# hub_exterior.net
KiCad netlist of a schematic drawn in EAGLE
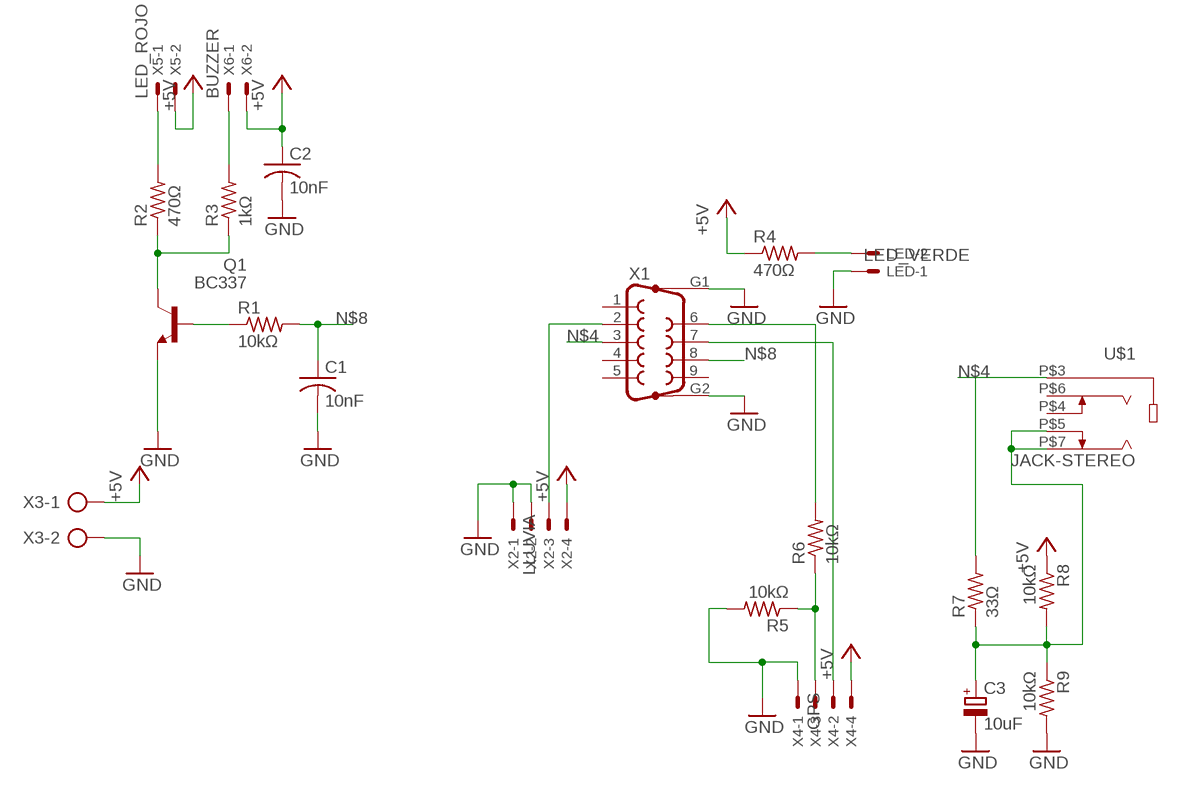
[diagram p0: schematic, sheet 1]

(export (version "E")
  (design (tool "Eeschema 10.0.6"))
  (components
    (comp (ref "C1")
      (value "10nF")
      (footprint "eagle-import:C050-025X075")
      (libsource (lib "eagle-import") (part "C-US050-025X075"))
    )
    (comp (ref "C2")
      (value "10nF")
      (footprint "eagle-import:C050-025X075")
      (libsource (lib "eagle-import") (part "C-US050-025X075"))
    )
    (comp (ref "C3")
      (value "10uF")
      (footprint "eagle-import:E2,5-5")
      (libsource (lib "eagle-import") (part "CPOL-EUE2.5-5"))
    )
    (comp (ref "LED")
      (value "LED_VERDE")
      (footprint "eagle-import:22-23-2021")
      (fields (field (name "MF") "MOLEX") (field (name "MPN") "22-23-2021"))
      (libsource (lib "eagle-import") (part "22-23-2021"))
    )
    (comp (ref "Q1")
      (value "BC337")
      (footprint "eagle-import:TO92")
      (libsource (lib "eagle-import") (part "BC337"))
    )
    (comp (ref "R1")
      (value "10kΩ")
      (footprint "eagle-import:0207_7")
      (libsource (lib "eagle-import") (part "R-US_0207/7"))
    )
    (comp (ref "R2")
      (value "470Ω")
      (footprint "eagle-import:0207_7")
      (libsource (lib "eagle-import") (part "R-US_0207/7"))
    )
    (comp (ref "R3")
      (value "1kΩ")
      (footprint "eagle-import:0207_7")
      (libsource (lib "eagle-import") (part "R-US_0207/7"))
    )
    (comp (ref "R4")
      (value "470Ω")
      (footprint "eagle-import:0207_7")
      (libsource (lib "eagle-import") (part "R-US_0207/7"))
    )
    (comp (ref "R5")
      (value "10kΩ")
      (footprint "eagle-import:0207_7")
      (libsource (lib "eagle-import") (part "R-US_0207/7"))
    )
    (comp (ref "R6")
      (value "10kΩ")
      (footprint "eagle-import:0207_15")
      (libsource (lib "eagle-import") (part "R-US_0207/15"))
    )
    (comp (ref "R7")
      (value "33Ω")
      (footprint "eagle-import:0207_7")
      (libsource (lib "eagle-import") (part "R-US_0207/7"))
    )
    (comp (ref "R8")
      (value "10kΩ")
      (footprint "eagle-import:0207_7")
      (libsource (lib "eagle-import") (part "R-US_0207/7"))
    )
    (comp (ref "R9")
      (value "10kΩ")
      (footprint "eagle-import:0207_7")
      (libsource (lib "eagle-import") (part "R-US_0207/7"))
    )
    (comp (ref "U$1")
      (value "JACK-STEREO")
      (footprint "eagle-import:SPC21348")
      (libsource (lib "eagle-import") (part "JACK-STEREO"))
    )
    (comp (ref "X1")
      (value "F09HP")
      (footprint "eagle-import:F09HP")
      (libsource (lib "eagle-import") (part "F09HP"))
    )
    (comp (ref "X2")
      (value "LLUVIA")
      (footprint "eagle-import:22-23-2041")
      (fields (field (name "MF") "MOLEX") (field (name "MPN") "22-23-2041"))
      (libsource (lib "eagle-import") (part "22-23-2041"))
    )
    (comp (ref "X3")
      (value "AK500/2")
      (footprint "eagle-import:AK500_2")
      (libsource (lib "eagle-import") (part "AK500/2"))
    )
    (comp (ref "X4")
      (value "GPS")
      (footprint "eagle-import:22-23-2041")
      (fields (field (name "MF") "MOLEX") (field (name "MPN") "22-23-2041"))
      (libsource (lib "eagle-import") (part "22-23-2041"))
    )
    (comp (ref "X5")
      (value "LED_ROJO")
      (footprint "eagle-import:22-23-2021")
      (fields (field (name "MF") "MOLEX") (field (name "MPN") "22-23-2021"))
      (libsource (lib "eagle-import") (part "22-23-2021"))
    )
    (comp (ref "X6")
      (value "BUZZER")
      (footprint "eagle-import:22-23-2021")
      (fields (field (name "MF") "MOLEX") (field (name "MPN") "22-23-2021"))
      (libsource (lib "eagle-import") (part "22-23-2021"))
    )
  )
  (nets
    (net (code "1") (name "+5V") (class "Default")
      (node (ref "C2") (pin "1") (pinfunction "1_1") (pintype "passive"))
      (node (ref "R4") (pin "1") (pinfunction "1_1") (pintype "passive"))
      (node (ref "R8") (pin "1") (pinfunction "1_1") (pintype "passive"))
      (node (ref "X2") (pin "4") (pinfunction "S_4") (pintype "passive"))
      (node (ref "X3") (pin "1") (pinfunction "KL_1") (pintype "passive"))
      (node (ref "X4") (pin "4") (pinfunction "S_4") (pintype "passive"))
      (node (ref "X5") (pin "2") (pinfunction "S_2") (pintype "passive"))
      (node (ref "X6") (pin "2") (pinfunction "S_2") (pintype "passive"))
    )
    (net (code "2") (name "/N$4") (class "Default")
      (node (ref "R7") (pin "2") (pinfunction "2_2") (pintype "passive"))
      (node (ref "U$1") (pin "P$3") (pinfunction "1_P$3") (pintype "passive"))
      (node (ref "X1") (pin "3") (pinfunction "3_3") (pintype "passive"))
    )
    (net (code "3") (name "/N$8") (class "Default")
      (node (ref "C1") (pin "1") (pinfunction "1_1") (pintype "passive"))
      (node (ref "R1") (pin "2") (pinfunction "2_2") (pintype "passive"))
      (node (ref "X1") (pin "8") (pinfunction "8_8") (pintype "passive"))
    )
    (net (code "4") (name "GND") (class "Default")
      (node (ref "C1") (pin "2") (pinfunction "2_2") (pintype "passive"))
      (node (ref "C2") (pin "2") (pinfunction "2_2") (pintype "passive"))
      (node (ref "C3") (pin "-") (pinfunction "-_-") (pintype "passive"))
      (node (ref "LED") (pin "1") (pinfunction "S_1") (pintype "passive"))
      (node (ref "Q1") (pin "1") (pinfunction "E_1") (pintype "passive"))
      (node (ref "R5") (pin "2") (pinfunction "2_2") (pintype "passive"))
      (node (ref "R9") (pin "2") (pinfunction "2_2") (pintype "passive"))
      (node (ref "X1") (pin "G1") (pinfunction "G1_G1") (pintype "passive"))
      (node (ref "X1") (pin "G2") (pinfunction "G2_G2") (pintype "passive"))
      (node (ref "X2") (pin "1") (pinfunction "S_1") (pintype "passive"))
      (node (ref "X2") (pin "2") (pinfunction "S_2") (pintype "passive"))
      (node (ref "X3") (pin "2") (pinfunction "KL_2") (pintype "passive"))
      (node (ref "X4") (pin "1") (pinfunction "S_1") (pintype "passive"))
    )
    (net (code "5") (name "Net-(LEDB-S)") (class "Default")
      (node (ref "LED") (pin "2") (pinfunction "S_2") (pintype "passive"))
      (node (ref "R4") (pin "2") (pinfunction "2_2") (pintype "passive"))
    )
    (net (code "6") (name "Net-(Q1-B)") (class "Default")
      (node (ref "Q1") (pin "2") (pinfunction "B_2") (pintype "passive"))
      (node (ref "R1") (pin "1") (pinfunction "1_1") (pintype "passive"))
    )
    (net (code "7") (name "Net-(Q1-C)") (class "Default")
      (node (ref "Q1") (pin "3") (pinfunction "C_3") (pintype "passive"))
      (node (ref "R2") (pin "1") (pinfunction "1_1") (pintype "passive"))
      (node (ref "R3") (pin "1") (pinfunction "1_1") (pintype "passive"))
    )
    (net (code "8") (name "Net-(R6-Pad2)") (class "Default")
      (node (ref "R6") (pin "2") (pinfunction "2_2") (pintype "passive"))
      (node (ref "X1") (pin "6") (pinfunction "6_6") (pintype "passive"))
    )
    (net (code "9") (name "Net-(U$1-4)") (class "Default")
      (node (ref "C3") (pin "+") (pinfunction "+_+") (pintype "passive"))
      (node (ref "R7") (pin "1") (pinfunction "1_1") (pintype "passive"))
      (node (ref "R8") (pin "2") (pinfunction "2_2") (pintype "passive"))
      (node (ref "R9") (pin "1") (pinfunction "1_1") (pintype "passive"))
      (node (ref "U$1") (pin "P$5") (pinfunction "4_P$5") (pintype "passive"))
      (node (ref "U$1") (pin "P$7") (pinfunction "5_P$7") (pintype "passive"))
    )
    (net (code "10") (name "Net-(X2C-S)") (class "Default")
      (node (ref "X1") (pin "2") (pinfunction "2_2") (pintype "passive"))
      (node (ref "X2") (pin "3") (pinfunction "S_3") (pintype "passive"))
    )
    (net (code "11") (name "Net-(X4B-S)") (class "Default")
      (node (ref "X1") (pin "7") (pinfunction "7_7") (pintype "passive"))
      (node (ref "X4") (pin "2") (pinfunction "S_2") (pintype "passive"))
    )
    (net (code "12") (name "Net-(X4C-S)") (class "Default")
      (node (ref "R5") (pin "1") (pinfunction "1_1") (pintype "passive"))
      (node (ref "R6") (pin "1") (pinfunction "1_1") (pintype "passive"))
      (node (ref "X4") (pin "3") (pinfunction "S_3") (pintype "passive"))
    )
    (net (code "13") (name "Net-(X5A-S)") (class "Default")
      (node (ref "R2") (pin "2") (pinfunction "2_2") (pintype "passive"))
      (node (ref "X5") (pin "1") (pinfunction "S_1") (pintype "passive"))
    )
    (net (code "14") (name "Net-(X6A-S)") (class "Default")
      (node (ref "R3") (pin "2") (pinfunction "2_2") (pintype "passive"))
      (node (ref "X6") (pin "1") (pinfunction "S_1") (pintype "passive"))
    )
    (net (code "15") (name "unconnected-(U$1-2-PadP$6)") (class "Default")
      (node (ref "U$1") (pin "P$6") (pinfunction "2_P$6") (pintype "passive"))
    )
    (net (code "16") (name "unconnected-(U$1-3-PadP$4)") (class "Default")
      (node (ref "U$1") (pin "P$4") (pinfunction "3_P$4") (pintype "passive"))
    )
    (net (code "17") (name "unconnected-(X1-Pad1)") (class "Default")
      (node (ref "X1") (pin "1") (pinfunction "1_1") (pintype "passive"))
    )
    (net (code "18") (name "unconnected-(X1-Pad4)") (class "Default")
      (node (ref "X1") (pin "4") (pinfunction "4_4") (pintype "passive"))
    )
    (net (code "19") (name "unconnected-(X1-Pad5)") (class "Default")
      (node (ref "X1") (pin "5") (pinfunction "5_5") (pintype "passive"))
    )
    (net (code "20") (name "unconnected-(X1-Pad9)") (class "Default")
      (node (ref "X1") (pin "9") (pinfunction "9_9") (pintype "passive"))
    )
  )
)
